# SCH_TRAFFICLIGHT.net
KiCad netlist of a schematic drawn in Altium Designer
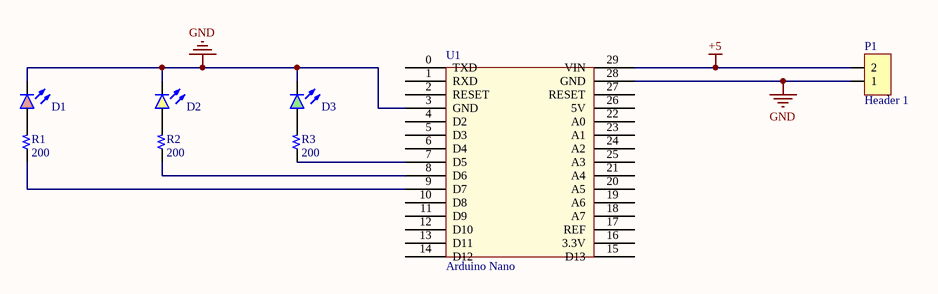
[diagram p0: SCH_TRAFFICLIGHT.SchDoc]

(export (version "E")
  (design (tool "Eeschema 10.0.6"))
  (components
    (comp (ref "D1")
      (value "LED RED")
      (footprint "LED 10MM - RED")
      (description "Typical LED 3-pin 2-color")
      (libsource (lib "led") (part "LED RED"))
    )
    (comp (ref "D2")
      (value "LED YELLOW")
      (footprint "LED 10MM - YELLOW")
      (description "Typical LED 3-pin 2-color")
      (libsource (lib "led") (part "LED YELLOW"))
    )
    (comp (ref "D3")
      (value "LED GREEN")
      (footprint "LED 10MM - GREEN")
      (description "Typical LED 3-pin 2-color")
      (libsource (lib "led") (part "LED GREEN"))
    )
    (comp (ref "P1")
      (value "Header 1")
      (footprint "HDR/Terminal/2")
      (description "Header, 2-Pin")
      (libsource (lib "connectors") (part "Header 2"))
    )
    (comp (ref "R1")
      (value "200")
      (footprint "R 1/4W/300")
      (description "Resistor")
      (libsource (lib "chipfc_libs") (part "Resistor"))
    )
    (comp (ref "R2")
      (value "200")
      (footprint "R 1/4W/300")
      (description "Resistor")
      (libsource (lib "chipfc_libs") (part "Resistor"))
    )
    (comp (ref "R3")
      (value "200")
      (footprint "R 1/4W/300")
      (description "Resistor")
      (libsource (lib "chipfc_libs") (part "Resistor"))
    )
    (comp (ref "U1")
      (value "Arduino Nano")
      (footprint "Arduino nano")
      (libsource (lib "nanoArduino") (part "arduinoNano"))
    )
  )
  (nets
    (net (code "1") (name "+5") (class "Default")
      (node (ref "P1") (pin "2") (pinfunction "2_2") (pintype "passive"))
      (node (ref "U1") (pin "29") (pinfunction "VIN_29") (pintype "passive"))
    )
    (net (code "2") (name "GND") (class "Default")
      (node (ref "D1") (pin "2") (pinfunction "K_2") (pintype "passive"))
      (node (ref "D2") (pin "2") (pinfunction "K_2") (pintype "passive"))
      (node (ref "D3") (pin "2") (pinfunction "K_2") (pintype "passive"))
      (node (ref "P1") (pin "1") (pinfunction "1_1") (pintype "passive"))
      (node (ref "U1") (pin "28") (pinfunction "GND_28") (pintype "passive"))
      (node (ref "U1") (pin "3") (pinfunction "GND_3") (pintype "passive"))
    )
    (net (code "3") (name "Net-(D1-A)") (class "Default")
      (node (ref "D1") (pin "1") (pinfunction "A_1") (pintype "passive"))
      (node (ref "R1") (pin "2") (pinfunction "2_2") (pintype "passive"))
    )
    (net (code "4") (name "Net-(D2-A)") (class "Default")
      (node (ref "D2") (pin "1") (pinfunction "A_1") (pintype "passive"))
      (node (ref "R2") (pin "2") (pinfunction "2_2") (pintype "passive"))
    )
    (net (code "5") (name "Net-(D3-A)") (class "Default")
      (node (ref "D3") (pin "1") (pinfunction "A_1") (pintype "passive"))
      (node (ref "R3") (pin "2") (pinfunction "2_2") (pintype "passive"))
    )
    (net (code "6") (name "Net-(U1-D5)") (class "Default")
      (node (ref "R3") (pin "1") (pinfunction "1_1") (pintype "passive"))
      (node (ref "U1") (pin "7") (pinfunction "D5_7") (pintype "passive"))
    )
    (net (code "7") (name "Net-(U1-D6)") (class "Default")
      (node (ref "R2") (pin "1") (pinfunction "1_1") (pintype "passive"))
      (node (ref "U1") (pin "8") (pinfunction "D6_8") (pintype "passive"))
    )
    (net (code "8") (name "Net-(U1-D7)") (class "Default")
      (node (ref "R1") (pin "1") (pinfunction "1_1") (pintype "passive"))
      (node (ref "U1") (pin "9") (pinfunction "D7_9") (pintype "passive"))
    )
    (net (code "9") (name "unconnected-(U1-3.3V-Pad16)") (class "Default")
      (node (ref "U1") (pin "16") (pinfunction "3.3V_16") (pintype "passive"))
    )
    (net (code "10") (name "unconnected-(U1-5V-Pad26)") (class "Default")
      (node (ref "U1") (pin "26") (pinfunction "5V_26") (pintype "passive"))
    )
    (net (code "11") (name "unconnected-(U1-A0-Pad22)") (class "Default")
      (node (ref "U1") (pin "22") (pinfunction "A0_22") (pintype "passive"))
    )
    (net (code "12") (name "unconnected-(U1-A1-Pad23)") (class "Default")
      (node (ref "U1") (pin "23") (pinfunction "A1_23") (pintype "passive"))
    )
    (net (code "13") (name "unconnected-(U1-A2-Pad24)") (class "Default")
      (node (ref "U1") (pin "24") (pinfunction "A2_24") (pintype "passive"))
    )
    (net (code "14") (name "unconnected-(U1-A3-Pad25)") (class "Default")
      (node (ref "U1") (pin "25") (pinfunction "A3_25") (pintype "passive"))
    )
    (net (code "15") (name "unconnected-(U1-A4-Pad21)") (class "Default")
      (node (ref "U1") (pin "21") (pinfunction "A4_21") (pintype "passive"))
    )
    (net (code "16") (name "unconnected-(U1-A5-Pad20)") (class "Default")
      (node (ref "U1") (pin "20") (pinfunction "A5_20") (pintype "passive"))
    )
    (net (code "17") (name "unconnected-(U1-A6-Pad19)") (class "Default")
      (node (ref "U1") (pin "19") (pinfunction "A6_19") (pintype "passive"))
    )
    (net (code "18") (name "unconnected-(U1-A7-Pad18)") (class "Default")
      (node (ref "U1") (pin "18") (pinfunction "A7_18") (pintype "passive"))
    )
    (net (code "19") (name "unconnected-(U1-D2-Pad4)") (class "Default")
      (node (ref "U1") (pin "4") (pinfunction "D2_4") (pintype "passive"))
    )
    (net (code "20") (name "unconnected-(U1-D3-Pad5)") (class "Default")
      (node (ref "U1") (pin "5") (pinfunction "D3_5") (pintype "passive"))
    )
    (net (code "21") (name "unconnected-(U1-D4-Pad6)") (class "Default")
      (node (ref "U1") (pin "6") (pinfunction "D4_6") (pintype "passive"))
    )
    (net (code "22") (name "unconnected-(U1-D8-Pad10)") (class "Default")
      (node (ref "U1") (pin "10") (pinfunction "D8_10") (pintype "passive"))
    )
    (net (code "23") (name "unconnected-(U1-D9-Pad11)") (class "Default")
      (node (ref "U1") (pin "11") (pinfunction "D9_11") (pintype "passive"))
    )
    (net (code "24") (name "unconnected-(U1-D10-Pad12)") (class "Default")
      (node (ref "U1") (pin "12") (pinfunction "D10_12") (pintype "passive"))
    )
    (net (code "25") (name "unconnected-(U1-D11-Pad13)") (class "Default")
      (node (ref "U1") (pin "13") (pinfunction "D11_13") (pintype "passive"))
    )
    (net (code "26") (name "unconnected-(U1-D12-Pad14)") (class "Default")
      (node (ref "U1") (pin "14") (pinfunction "D12_14") (pintype "passive"))
    )
    (net (code "27") (name "unconnected-(U1-D13-Pad15)") (class "Default")
      (node (ref "U1") (pin "15") (pinfunction "D13_15") (pintype "passive"))
    )
    (net (code "28") (name "unconnected-(U1-REF-Pad17)") (class "Default")
      (node (ref "U1") (pin "17") (pinfunction "REF_17") (pintype "passive"))
    )
    (net (code "29") (name "unconnected-(U1-RESET-Pad2)") (class "Default")
      (node (ref "U1") (pin "2") (pinfunction "RESET_2") (pintype "passive"))
    )
    (net (code "30") (name "unconnected-(U1-RESET-Pad27)") (class "Default")
      (node (ref "U1") (pin "27") (pinfunction "RESET_27") (pintype "passive"))
    )
    (net (code "31") (name "unconnected-(U1-RXD-Pad1)") (class "Default")
      (node (ref "U1") (pin "1") (pinfunction "RXD_1") (pintype "passive"))
    )
    (net (code "32") (name "unconnected-(U1-TXD-Pad0)") (class "Default")
      (node (ref "U1") (pin "0") (pinfunction "TXD_0") (pintype "passive"))
    )
  )
)
